# capstone_v1_1.net
KiCad netlist of a schematic drawn in Altium Designer
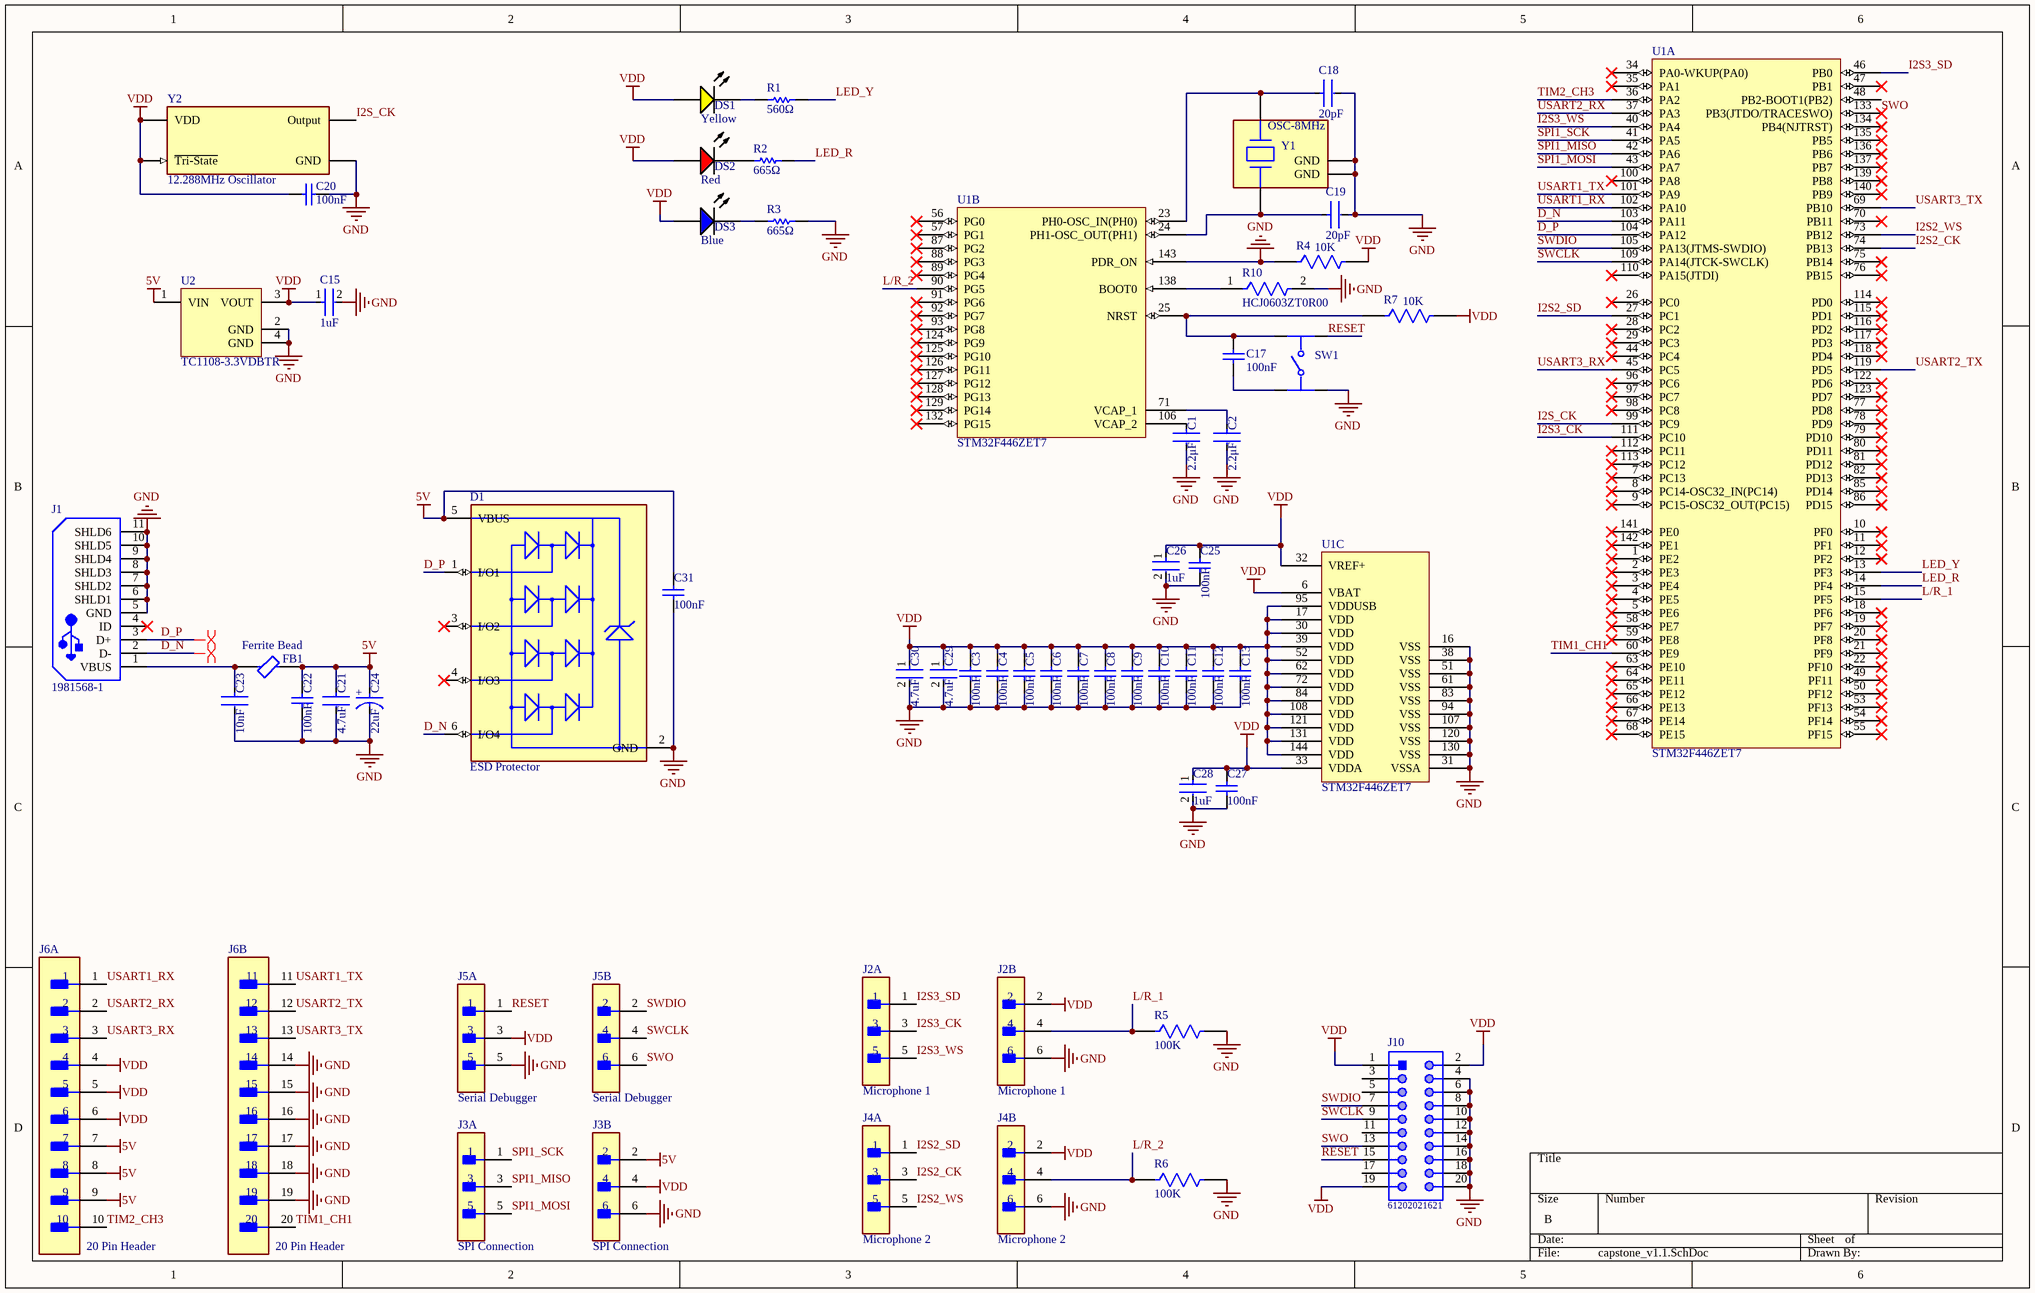
[diagram p0: capstone_v1.1.SchDoc]

(export (version "E")
  (design (tool "Eeschema 10.0.6"))
  (components
    (comp (ref "C1")
      (value "2.2μF")
      (footprint "FP-C1608-080-0_1-MFG")
      (description "Multilayer Ceramic Capacitors 2.2μF ±10% 35V X5R SMD 0603\r\nC1608X5R1V225K080AC")
      (fields (field (name "TOLERANCE") "10%") (field (name "VOLTAGE") "35V"))
      (libsource (lib "Altium Content Vault") (part "236180d848d6139a670b325ea6854c9"))
    )
    (comp (ref "C2")
      (value "2.2μF")
      (footprint "FP-C1608-080-0_1-MFG")
      (description "Multilayer Ceramic Capacitors 2.2μF ±10% 35V X5R SMD 0603\r\nC1608X5R1V225K080AC")
      (fields (field (name "TOLERANCE") "10%") (field (name "VOLTAGE") "35V"))
      (libsource (lib "Altium Content Vault") (part "236180d848d6139a670b325ea6854c9"))
    )
    (comp (ref "C3")
      (value "100nF")
      (footprint "SAMS-C0603-2_M")
      (fields (field (name "MANUFACTURER") "Samsung Electro-Mechanics"))
      (libsource (lib "Altium Content Vault") (part "CAP-NP-2"))
    )
    (comp (ref "C4")
      (value "100nF")
      (footprint "SAMS-C0603-2_M")
      (fields (field (name "MANUFACTURER") "Samsung Electro-Mechanics"))
      (libsource (lib "Altium Content Vault") (part "CAP-NP-2"))
    )
    (comp (ref "C5")
      (value "100nF")
      (footprint "SAMS-C0603-2_M")
      (fields (field (name "MANUFACTURER") "Samsung Electro-Mechanics"))
      (libsource (lib "Altium Content Vault") (part "CAP-NP-2"))
    )
    (comp (ref "C6")
      (value "100nF")
      (footprint "SAMS-C0603-2_M")
      (fields (field (name "MANUFACTURER") "Samsung Electro-Mechanics"))
      (libsource (lib "Altium Content Vault") (part "CAP-NP-2"))
    )
    (comp (ref "C7")
      (value "100nF")
      (footprint "SAMS-C0603-2_M")
      (fields (field (name "MANUFACTURER") "Samsung Electro-Mechanics"))
      (libsource (lib "Altium Content Vault") (part "CAP-NP-2"))
    )
    (comp (ref "C8")
      (value "100nF")
      (footprint "SAMS-C0603-2_M")
      (fields (field (name "MANUFACTURER") "Samsung Electro-Mechanics"))
      (libsource (lib "Altium Content Vault") (part "CAP-NP-2"))
    )
    (comp (ref "C9")
      (value "100nF")
      (footprint "SAMS-C0603-2_M")
      (fields (field (name "MANUFACTURER") "Samsung Electro-Mechanics"))
      (libsource (lib "Altium Content Vault") (part "CAP-NP-2"))
    )
    (comp (ref "C10")
      (value "100nF")
      (footprint "SAMS-C0603-2_M")
      (fields (field (name "MANUFACTURER") "Samsung Electro-Mechanics"))
      (libsource (lib "Altium Content Vault") (part "CAP-NP-2"))
    )
    (comp (ref "C11")
      (value "100nF")
      (footprint "SAMS-C0603-2_M")
      (fields (field (name "MANUFACTURER") "Samsung Electro-Mechanics"))
      (libsource (lib "Altium Content Vault") (part "CAP-NP-2"))
    )
    (comp (ref "C12")
      (value "100nF")
      (footprint "SAMS-C0603-2_M")
      (fields (field (name "MANUFACTURER") "Samsung Electro-Mechanics"))
      (libsource (lib "Altium Content Vault") (part "CAP-NP-2"))
    )
    (comp (ref "C13")
      (value "100nF")
      (footprint "SAMS-C0603-2_M")
      (fields (field (name "MANUFACTURER") "Samsung Electro-Mechanics"))
      (libsource (lib "Altium Content Vault") (part "CAP-NP-2"))
    )
    (comp (ref "C15")
      (value "1uF")
      (footprint "FP-0603-L_1_6_0_15-W_0_81-IPC_A")
      (description "General Purpose Ceramic Capacitor, 0603, 1uF, 10%, X5R, 15%, 10V\r\n0603ZD105KAT2A")
      (fields (field (name "TOLERANCE") "10%") (field (name "VOLTAGE") "10V"))
      (libsource (lib "Altium Content Vault") (part "02cd4be3c70576c341d710602a673aa"))
    )
    (comp (ref "C17")
      (value "100nF")
      (footprint "SAMS-C0603-2_M")
      (fields (field (name "MANUFACTURER") "Samsung Electro-Mechanics"))
      (libsource (lib "Altium Content Vault") (part "CAP-NP-2"))
    )
    (comp (ref "C18")
      (value "20pF")
      (footprint "FP-C0603C-CF-MFG")
      (description "CAP CER 20PF 50V 5% NP0 0603\r\nC0603C200J5GACTU")
      (fields
        (field (name "MANUFACTURER PART NUMBER") "C0603C200J5GACTU")
        (field (name "MANUFACTURER") "KEMET")
      )
      (libsource (lib "Altium Content Vault") (part "b4654b650e69147ec39a6b967a45e02"))
    )
    (comp (ref "C19")
      (value "20pF")
      (footprint "FP-C0603C-CF-MFG")
      (description "CAP CER 20PF 50V 5% NP0 0603\r\nC0603C200J5GACTU")
      (fields
        (field (name "MANUFACTURER PART NUMBER") "C0603C200J5GACTU")
        (field (name "MANUFACTURER") "KEMET")
      )
      (libsource (lib "Altium Content Vault") (part "b4654b650e69147ec39a6b967a45e02"))
    )
    (comp (ref "C20")
      (value "100nF")
      (footprint "SAMS-C0603-2_M")
      (fields (field (name "MANUFACTURER") "Samsung Electro-Mechanics"))
      (libsource (lib "Altium Content Vault") (part "CAP-NP-2"))
    )
    (comp (ref "C21")
      (value "4.7uF")
      (footprint "FP-C0603-CG-MFG")
      (description "CAP CER 4.7UF 6.3V X5R 0603\r\nC0603C475K9PACTU")
      (fields (field (name "TOLERANCE") "10%") (field (name "MANUFACTURER") "Kemet"))
      (libsource (lib "") (part "11868f565c42a9108669ba33697ecf6_1"))
    )
    (comp (ref "C22")
      (value "100nF")
      (footprint "SAMS-C0603-2_M")
      (fields (field (name "MANUFACTURER") "Samsung Electro-Mechanics"))
      (libsource (lib "Altium Content Vault") (part "CAP-NP-2"))
    )
    (comp (ref "C23")
      (value "10nF")
      (footprint "FP-0603-L_1_6_0_15-W_0_81-MFG")
      (description "General Purpose Ceramic Capacitor, 0603, 10nF, 10%, X7R, 15%, 50V")
      (fields (field (name "VOLTAGE") "50V") (field (name "TOLERANCE") "10%"))
      (libsource (lib "") (part "02cd4be3c70576c341d710602a673aa_1"))
    )
    (comp (ref "C24")
      (value "22uF")
      (footprint "FP-T491C226K010AT-MFG")
      (description "CAP TANT 22UF 10% 10V 2312\r\nT491C226K010AT")
      (fields (field (name "TOLERANCE") "20%") (field (name "VOLTAGE") "10V"))
      (libsource (lib "Altium Content Vault") (part "a00bbbee19879c290e62620ae7e47b1"))
    )
    (comp (ref "C25")
      (value "100nF")
      (footprint "SAMS-C0603-2_M")
      (fields (field (name "MANUFACTURER") "Samsung Electro-Mechanics"))
      (libsource (lib "Altium Content Vault") (part "CAP-NP-2"))
    )
    (comp (ref "C26")
      (value "1uF")
      (footprint "FP-0603-L_1_6_0_15-W_0_81-IPC_A")
      (description "General Purpose Ceramic Capacitor, 0603, 1uF, 10%, X5R, 15%, 10V\r\n0603ZD105KAT2A")
      (fields (field (name "TOLERANCE") "10%") (field (name "VOLTAGE") "10V"))
      (libsource (lib "Altium Content Vault") (part "02cd4be3c70576c341d710602a673aa"))
    )
    (comp (ref "C27")
      (value "100nF")
      (footprint "SAMS-C0603-2_M")
      (fields (field (name "MANUFACTURER") "Samsung Electro-Mechanics"))
      (libsource (lib "Altium Content Vault") (part "CAP-NP-2"))
    )
    (comp (ref "C28")
      (value "1uF")
      (footprint "FP-0603-L_1_6_0_15-W_0_81-IPC_A")
      (description "General Purpose Ceramic Capacitor, 0603, 1uF, 10%, X5R, 15%, 10V\r\n0603ZD105KAT2A")
      (fields (field (name "TOLERANCE") "10%") (field (name "VOLTAGE") "10V"))
      (libsource (lib "Altium Content Vault") (part "02cd4be3c70576c341d710602a673aa"))
    )
    (comp (ref "C29")
      (value "4.7uF")
      (footprint "FP-C0603-CG-MFG")
      (description "CAP CER 4.7UF 6.3V X5R 0603\r\nC0603C475K9PACTU")
      (fields (field (name "TOLERANCE") "10%") (field (name "MANUFACTURER") "Kemet"))
      (libsource (lib "Altium Content Vault") (part "11868f565c42a9108669ba33697ecf6"))
    )
    (comp (ref "C30")
      (value "4.7uF")
      (footprint "FP-C0603-CG-MFG")
      (description "CAP CER 4.7UF 6.3V X5R 0603\r\nC0603C475K9PACTU")
      (fields (field (name "TOLERANCE") "10%") (field (name "MANUFACTURER") "Kemet"))
      (libsource (lib "Altium Content Vault") (part "11868f565c42a9108669ba33697ecf6"))
    )
    (comp (ref "C31")
      (value "100nF")
      (footprint "SAMS-C0603-2_M")
      (fields (field (name "MANUFACTURER") "Samsung Electro-Mechanics"))
      (libsource (lib "Altium Content Vault") (part "CAP-NP-2"))
    )
    (comp (ref "D1")
      (value "ESD Protector")
      (footprint "FP-SOT23-6L-MFG")
      (description "TVS DIODE 5.25V 17V SOT23-6\r\nUSBLC6-4SC6")
      (fields
        (field (name "MANUFACTURER") "STMicroelectronics")
        (field (name "OCTOPART") "https://octopart.com/usblc6-4sc6-stmicroelectronics-347147")
      )
      (libsource (lib "Altium Content Vault") (part "3e70b616ccdc4c88b528e1820c4a7da"))
    )
    (comp (ref "DS1")
      (value "Yellow")
      (footprint "VISH-TLMY1000_V")
      (description "Low Current LED, 40 mW, -40 to 100 degC, 2-Pin SMD, RoHS, Tape and Reel\r\nTLMY1000-GS08")
      (fields (field (name "MANUFACTURER") "Vishay"))
      (libsource (lib "Altium Content Vault") (part "LED-YELLOW-AK-2"))
    )
    (comp (ref "DS2")
      (value "Red")
      (footprint "AVAG-HSMX-C190_V")
      (description "LED Uni-Color Red, 65 mW, 20 mA, -40 to 85 degC, 2-Pin SMD, RoHS, Tape and Reel\r\nHSMH-C190")
      (libsource (lib "Altium Content Vault") (part "LED-RED-AK-2"))
    )
    (comp (ref "DS3")
      (value "Blue")
      (footprint "AVAG-HSMX-C190_V")
      (description "LED Uni-Color Blue, 78 mW, 20 mA, -40 to 85 degC, 2-Pin SMD, RoHS, Tape and Reel\r\nHSMR-C190")
      (libsource (lib "Altium Content Vault") (part "LED-BLUE-AK-2"))
    )
    (comp (ref "FB1")
      (value "Ferrite Bead")
      (footprint "FP-BLM15-0_05-IPC_A")
      (description "Chip Ferrite Bead, 0402, 220Ω @ 100MHz, 0.1Ω, 25%, 1.4A\r\nBLM15PX221SN1D")
      (fields (field (name "TOLERANCE") "25%"))
      (libsource (lib "Altium Content Vault") (part "5f30dd21d616792df468990f7003faa"))
    )
    (comp (ref "J1")
      (value "1981568-1")
      (footprint "TECO-1981568-5_V")
      (description "Micro USB Receptacle Standard Type B Assy, 5-Pin SMD, RoHS, Tape and Reel")
      (fields (field (name "MANUFACTURER") "TE Connectivity"))
      (libsource (lib "Altium Content Vault") (part "USB-5-6SHLD"))
    )
    (comp (ref "J2")
      (value "Microphone 1")
      (footprint "FP-M20-9980346-MFG")
      (description "CONN HEADER VERT 6POS 2.54MM\r\nM20-9980346")
      (fields (field (name "MANUFACTURER PART NUMBER") "M20-9980346") (field (name "MANUFACTURER") "Harwin"))
      (libsource (lib "Altium Content Vault") (part "2654a11fb13586ecb194516b1c997bc"))
    )
    (comp (ref "J3")
      (value "SPI Connection")
      (footprint "FP-M20-9980346-MFG")
      (description "CONN HEADER VERT 6POS 2.54MM\r\nM20-9980346")
      (fields (field (name "MANUFACTURER PART NUMBER") "M20-9980346") (field (name "MANUFACTURER") "Harwin"))
      (libsource (lib "Altium Content Vault") (part "2654a11fb13586ecb194516b1c997bc"))
    )
    (comp (ref "J4")
      (value "Microphone 2")
      (footprint "FP-M20-9980346-MFG")
      (description "CONN HEADER VERT 6POS 2.54MM\r\nM20-9980346")
      (fields (field (name "MANUFACTURER PART NUMBER") "M20-9980346") (field (name "MANUFACTURER") "Harwin"))
      (libsource (lib "Altium Content Vault") (part "2654a11fb13586ecb194516b1c997bc"))
    )
    (comp (ref "J5")
      (value "Serial Debugger")
      (footprint "FP-M20-9980346-MFG")
      (description "CONN HEADER VERT 6POS 2.54MM\r\nM20-9980346")
      (fields (field (name "MANUFACTURER PART NUMBER") "M20-9980346") (field (name "MANUFACTURER") "Harwin"))
      (libsource (lib "Altium Content Vault") (part "2654a11fb13586ecb194516b1c997bc"))
    )
    (comp (ref "J6")
      (value "20 Pin Header")
      (footprint "FP-TSW-110-08-G-D-MFG")
      (description "CONN HEADER VERT 20POS 2.54MM\r\nTSW-110-08-G-D")
      (fields
        (field (name "MANUFACTURER") "Samtec")
        (field (name "MANUFACTURER PART NUMBER") "TSW-110-08-G-D")
      )
      (libsource (lib "Altium Content Vault") (part "77e5b6e48cf913a9c6d5f7856d88bd2"))
    )
    (comp (ref "J10")
      (value "61202021621")
      (footprint "61202021621")
      (description "Male Box Header WR-BHD, THT, Vertical, pitch 2.54 mm, 20 pins")
      (fields (field (name "MANUFACTURER") "Wurth Elektronik") (field (name "PUBLISHER") "WurthElektronik"))
      (libsource (lib "Altium Content Vault") (part "WE-CN-2P-M-R20"))
    )
    (comp (ref "R1")
      (value "560Ω")
      (footprint "RESC1608X55X30ML15T15")
      (libsource (lib "Altium Content Vault") (part "RES-2"))
    )
    (comp (ref "R2")
      (value "665Ω")
      (footprint "RESC1608X55X30ML15T15")
      (description "ERJ-3EKF6650V")
      (fields (field (name "MANUFACTURER") "Panasonic"))
      (libsource (lib "Altium Content Vault") (part "RES"))
    )
    (comp (ref "R3")
      (value "665Ω")
      (footprint "RESC1608X55X30ML15T15")
      (description "ERJ-3EKF6650V")
      (fields (field (name "MANUFACTURER") "Panasonic"))
      (libsource (lib "Altium Content Vault") (part "RES"))
    )
    (comp (ref "R4")
      (value "10K")
      (footprint "FP-MCT0603-IPC_C")
      (description "RES SMD 100 OHM 1% 1/8W 0603\r\nMCT06030C1002FP500")
      (fields (field (name "TOLERANCE") "1%"))
      (libsource (lib "Altium Content Vault") (part "1029c3af85768c4190bb7ad29bc67b5"))
    )
    (comp (ref "R5")
      (value "100K")
      (footprint "FP-RC0603-0_55-MFG")
      (description "RES SMD 100K OHM 1% 1/10W 0603\r\nRC0603FR-07100KL")
      (fields (field (name "TOLERANCE") "1%"))
      (libsource (lib "Altium Content Vault") (part "1029c3af85768c4190bb7ad29bc67b5"))
    )
    (comp (ref "R6")
      (value "100K")
      (footprint "FP-RC0603-0_55-MFG")
      (description "RES SMD 100K OHM 1% 1/10W 0603\r\nRC0603FR-07100KL")
      (fields (field (name "TOLERANCE") "1%"))
      (libsource (lib "Altium Content Vault") (part "1029c3af85768c4190bb7ad29bc67b5"))
    )
    (comp (ref "R7")
      (value "10K")
      (footprint "FP-MCT0603-IPC_C")
      (description "RES SMD 100 OHM 1% 1/8W 0603\r\nMCT06030C1002FP500")
      (fields (field (name "TOLERANCE") "1%"))
      (libsource (lib "Altium Content Vault") (part "1029c3af85768c4190bb7ad29bc67b5"))
    )
    (comp (ref "R10")
      (value "HCJ0603ZT0R00")
      (footprint "FP-HCJ0603-MFG")
      (description "RES 0 OHM JUMPER 1/4W 0603")
      (libsource (lib "") (part "1029c3af85768c4190bb7ad29bc67b5_1"))
    )
    (comp (ref "SW1")
      (value "PTS645SM43SMTR92LFS")
      (footprint "FP-PTS645SM43SMTR92LFS-MFG")
      (description "SWITCH TACTILE SPST-NO 0.05A 12V")
      (libsource (lib "Altium Content Vault") (part "1adf0dd01260c80cf25a44bfd6b99ba"))
    )
    (comp (ref "U1")
      (value "STM32F446ZET7")
      (footprint "STM-LQFP144_M")
      (libsource (lib "Altium Content Vault") (part "MC-ARM-STM32F446-LQFP144"))
    )
    (comp (ref "U2")
      (value "TC1108-3.3VDBTR")
      (footprint "SOT-223-DB3_L")
      (description "300mA CMOS LDO, 3-Pin SOT-223, Extended Temperature, Tape and Reel")
      (libsource (lib "Altium Content Vault") (part "PM-LINEREG-TC1108-IL4"))
    )
    (comp (ref "Y1")
      (value "OSC-8MHz")
      (footprint "FP-ABM3B-MFG")
      (description "Crystal 8MHz ±20ppm 18pF SMD-4 5mm x 3.2mm\r\nABM3B-8.000MHZ-B2-T")
      (fields (field (name "TOLERANCE") "20ppm"))
      (libsource (lib "Altium Content Vault") (part "48e526d86b7f2615d98721063c72f49"))
    )
    (comp (ref "Y2")
      (value "12.288MHz Oscillator")
      (footprint "FP-ASFL1-MFG")
      (description "XTAL Oscillator 12.288MHz ±50ppm HCMOS, TTL 3.3V 4-SMD 5mm x 3.2mm\r\nASFL1-12.288MHZ-EC-T")
      (libsource (lib "Altium Content Vault") (part "47df00dc2349451232cb22fac08fbff"))
    )
  )
  (nets
    (net (code "1") (name "/D_N") (class "Default")
      (node (ref "D1") (pin "6") (pinfunction "I/O4_6") (pintype "bidirectional"))
      (node (ref "J1") (pin "2") (pinfunction "D-_2") (pintype "passive"))
      (node (ref "U1") (pin "103") (pinfunction "PA11_103") (pintype "bidirectional"))
    )
    (net (code "2") (name "/D_P") (class "Default")
      (node (ref "D1") (pin "1") (pinfunction "I/O1_1") (pintype "bidirectional"))
      (node (ref "J1") (pin "3") (pinfunction "D+_3") (pintype "passive"))
      (node (ref "U1") (pin "104") (pinfunction "PA12_104") (pintype "bidirectional"))
    )
    (net (code "3") (name "/I2S2_CK") (class "Default")
      (node (ref "J4") (pin "3") (pinfunction "3_3") (pintype "passive"))
      (node (ref "U1") (pin "74") (pinfunction "PB13_74") (pintype "bidirectional"))
    )
    (net (code "4") (name "/I2S2_SD") (class "Default")
      (node (ref "J4") (pin "1") (pinfunction "1_1") (pintype "passive"))
      (node (ref "U1") (pin "27") (pinfunction "PC1_27") (pintype "bidirectional"))
    )
    (net (code "5") (name "/I2S2_WS") (class "Default")
      (node (ref "J4") (pin "5") (pinfunction "5_5") (pintype "passive"))
      (node (ref "U1") (pin "73") (pinfunction "PB12_73") (pintype "bidirectional"))
    )
    (net (code "6") (name "/I2S3_CK") (class "Default")
      (node (ref "J2") (pin "3") (pinfunction "3_3") (pintype "passive"))
      (node (ref "U1") (pin "111") (pinfunction "PC10_111") (pintype "bidirectional"))
    )
    (net (code "7") (name "/I2S3_SD") (class "Default")
      (node (ref "J2") (pin "1") (pinfunction "1_1") (pintype "passive"))
      (node (ref "U1") (pin "46") (pinfunction "PB0_46") (pintype "bidirectional"))
    )
    (net (code "8") (name "/I2S3_WS") (class "Default")
      (node (ref "J2") (pin "5") (pinfunction "5_5") (pintype "passive"))
      (node (ref "U1") (pin "40") (pinfunction "PA4_40") (pintype "bidirectional"))
    )
    (net (code "9") (name "/I2S_CK") (class "Default")
      (node (ref "U1") (pin "99") (pinfunction "PC9_99") (pintype "bidirectional"))
      (node (ref "Y2") (pin "3") (pinfunction "Output_3") (pintype "passive"))
    )
    (net (code "10") (name "/LED_R") (class "Default")
      (node (ref "R2") (pin "2") (pinfunction "2_2") (pintype "passive"))
      (node (ref "U1") (pin "14") (pinfunction "PF4_14") (pintype "bidirectional"))
    )
    (net (code "11") (name "/LED_Y") (class "Default")
      (node (ref "R1") (pin "2") (pinfunction "2_2") (pintype "passive"))
      (node (ref "U1") (pin "13") (pinfunction "PF3_13") (pintype "bidirectional"))
    )
    (net (code "12") (name "/L{slash}R_1") (class "Default")
      (node (ref "J2") (pin "4") (pinfunction "4_4") (pintype "passive"))
      (node (ref "R5") (pin "1") (pinfunction "1_1") (pintype "passive"))
      (node (ref "U1") (pin "15") (pinfunction "PF5_15") (pintype "bidirectional"))
    )
    (net (code "13") (name "/L{slash}R_2") (class "Default")
      (node (ref "J4") (pin "4") (pinfunction "4_4") (pintype "passive"))
      (node (ref "R6") (pin "1") (pinfunction "1_1") (pintype "passive"))
      (node (ref "U1") (pin "90") (pinfunction "PG5_90") (pintype "bidirectional"))
    )
    (net (code "14") (name "/RESET") (class "Default")
      (node (ref "J10") (pin "15") (pinfunction "15_15") (pintype "passive"))
      (node (ref "J5") (pin "1") (pinfunction "1_1") (pintype "passive"))
      (node (ref "SW1") (pin "2") (pinfunction "2_2") (pintype "passive"))
    )
    (net (code "15") (name "/SPI1_MISO") (class "Default")
      (node (ref "J3") (pin "3") (pinfunction "3_3") (pintype "passive"))
      (node (ref "U1") (pin "42") (pinfunction "PA6_42") (pintype "bidirectional"))
    )
    (net (code "16") (name "/SPI1_MOSI") (class "Default")
      (node (ref "J3") (pin "5") (pinfunction "5_5") (pintype "passive"))
      (node (ref "U1") (pin "43") (pinfunction "PA7_43") (pintype "bidirectional"))
    )
    (net (code "17") (name "/SPI1_SCK") (class "Default")
      (node (ref "J3") (pin "1") (pinfunction "1_1") (pintype "passive"))
      (node (ref "U1") (pin "41") (pinfunction "PA5_41") (pintype "bidirectional"))
    )
    (net (code "18") (name "/SWCLK") (class "Default")
      (node (ref "J10") (pin "9") (pinfunction "9_9") (pintype "passive"))
      (node (ref "J5") (pin "4") (pinfunction "4_4") (pintype "passive"))
      (node (ref "U1") (pin "109") (pinfunction "PA14(JTCK-SWCLK)_109") (pintype "bidirectional"))
    )
    (net (code "19") (name "/SWDIO") (class "Default")
      (node (ref "J10") (pin "7") (pinfunction "7_7") (pintype "passive"))
      (node (ref "J5") (pin "2") (pinfunction "2_2") (pintype "passive"))
      (node (ref "U1") (pin "105") (pinfunction "PA13(JTMS-SWDIO)_105") (pintype "bidirectional"))
    )
    (net (code "20") (name "/SWO") (class "Default")
      (node (ref "J10") (pin "13") (pinfunction "13_13") (pintype "passive"))
      (node (ref "J5") (pin "6") (pinfunction "6_6") (pintype "passive"))
      (node (ref "U1") (pin "133") (pinfunction "PB3(JTDO/TRACESWO)_133") (pintype "bidirectional"))
    )
    (net (code "21") (name "/TIM1_CH1") (class "Default")
      (node (ref "J6") (pin "20") (pinfunction "20_20") (pintype "passive"))
      (node (ref "U1") (pin "60") (pinfunction "PE9_60") (pintype "bidirectional"))
    )
    (net (code "22") (name "/TIM2_CH3") (class "Default")
      (node (ref "J6") (pin "10") (pinfunction "10_10") (pintype "passive"))
      (node (ref "U1") (pin "36") (pinfunction "PA2_36") (pintype "bidirectional"))
    )
    (net (code "23") (name "/USART1_RX") (class "Default")
      (node (ref "J6") (pin "1") (pinfunction "1_1") (pintype "passive"))
      (node (ref "U1") (pin "102") (pinfunction "PA10_102") (pintype "bidirectional"))
    )
    (net (code "24") (name "/USART1_TX") (class "Default")
      (node (ref "J6") (pin "11") (pinfunction "11_11") (pintype "passive"))
      (node (ref "U1") (pin "101") (pinfunction "PA9_101") (pintype "bidirectional"))
    )
    (net (code "25") (name "/USART2_RX") (class "Default")
      (node (ref "J6") (pin "2") (pinfunction "2_2") (pintype "passive"))
      (node (ref "U1") (pin "37") (pinfunction "PA3_37") (pintype "bidirectional"))
    )
    (net (code "26") (name "/USART2_TX") (class "Default")
      (node (ref "J6") (pin "12") (pinfunction "12_12") (pintype "passive"))
      (node (ref "U1") (pin "119") (pinfunction "PD5_119") (pintype "bidirectional"))
    )
    (net (code "27") (name "/USART3_RX") (class "Default")
      (node (ref "J6") (pin "3") (pinfunction "3_3") (pintype "passive"))
      (node (ref "U1") (pin "45") (pinfunction "PC5_45") (pintype "bidirectional"))
    )
    (net (code "28") (name "/USART3_TX") (class "Default")
      (node (ref "J6") (pin "13") (pinfunction "13_13") (pintype "passive"))
      (node (ref "U1") (pin "69") (pinfunction "PB10_69") (pintype "bidirectional"))
    )
    (net (code "29") (name "5V") (class "Default")
      (node (ref "C21") (pin "1") (pinfunction "1_1") (pintype "passive"))
      (node (ref "C22") (pin "2") (pinfunction "2_2") (pintype "passive"))
      (node (ref "C24") (pin "2") (pinfunction "A_2") (pintype "passive"))
      (node (ref "C31") (pin "2") (pinfunction "2_2") (pintype "passive"))
      (node (ref "D1") (pin "5") (pinfunction "VBUS_5") (pintype "power_in"))
      (node (ref "FB1") (pin "2") (pinfunction "2_2") (pintype "passive"))
      (node (ref "J3") (pin "2") (pinfunction "2_2") (pintype "passive"))
      (node (ref "J6") (pin "7") (pinfunction "7_7") (pintype "passive"))
      (node (ref "J6") (pin "8") (pinfunction "8_8") (pintype "passive"))
      (node (ref "J6") (pin "9") (pinfunction "9_9") (pintype "passive"))
      (node (ref "U2") (pin "1") (pinfunction "VIN_1") (pintype "power_in"))
    )
    (net (code "30") (name "GND") (class "Default")
      (node (ref "C1") (pin "1") (pinfunction "1_1") (pintype "passive"))
      (node (ref "C10") (pin "1") (pinfunction "1_1") (pintype "passive"))
      (node (ref "C11") (pin "1") (pinfunction "1_1") (pintype "passive"))
      (node (ref "C12") (pin "1") (pinfunction "1_1") (pintype "passive"))
      (node (ref "C13") (pin "1") (pinfunction "1_1") (pintype "passive"))
      (node (ref "C15") (pin "2") (pinfunction "2_2") (pintype "passive"))
      (node (ref "C18") (pin "2") (pinfunction "2_2") (pintype "passive"))
      (node (ref "C19") (pin "2") (pinfunction "2_2") (pintype "passive"))
      (node (ref "C2") (pin "1") (pinfunction "1_1") (pintype "passive"))
      (node (ref "C20") (pin "1") (pinfunction "1_1") (pintype "passive"))
      (node (ref "C21") (pin "2") (pinfunction "2_2") (pintype "passive"))
      (node (ref "C22") (pin "1") (pinfunction "1_1") (pintype "passive"))
      (node (ref "C23") (pin "2") (pinfunction "2_2") (pintype "passive"))
      (node (ref "C24") (pin "1") (pinfunction "C_1") (pintype "passive"))
      (node (ref "C25") (pin "1") (pinfunction "1_1") (pintype "passive"))
      (node (ref "C26") (pin "2") (pinfunction "2_2") (pintype "passive"))
      (node (ref "C27") (pin "1") (pinfunction "1_1") (pintype "passive"))
      (node (ref "C28") (pin "2") (pinfunction "2_2") (pintype "passive"))
      (node (ref "C29") (pin "2") (pinfunction "2_2") (pintype "passive"))
      (node (ref "C3") (pin "1") (pinfunction "1_1") (pintype "passive"))
      (node (ref "C30") (pin "2") (pinfunction "2_2") (pintype "passive"))
      (node (ref "C31") (pin "1") (pinfunction "1_1") (pintype "passive"))
      (node (ref "C4") (pin "1") (pinfunction "1_1") (pintype "passive"))
      (node (ref "C5") (pin "1") (pinfunction "1_1") (pintype "passive"))
      (node (ref "C6") (pin "1") (pinfunction "1_1") (pintype "passive"))
      (node (ref "C7") (pin "1") (pinfunction "1_1") (pintype "passive"))
      (node (ref "C8") (pin "1") (pinfunction "1_1") (pintype "passive"))
      (node (ref "C9") (pin "1") (pinfunction "1_1") (pintype "passive"))
      (node (ref "D1") (pin "2") (pinfunction "GND_2") (pintype "power_in"))
      (node (ref "J1") (pin "10") (pinfunction "SHLD5_10") (pintype "passive"))
      (node (ref "J1") (pin "11") (pinfunction "SHLD6_11") (pintype "passive"))
      (node (ref "J1") (pin "5") (pinfunction "GND_5") (pintype "passive"))
      (node (ref "J1") (pin "6") (pinfunction "SHLD1_6") (pintype "passive"))
      (node (ref "J1") (pin "7") (pinfunction "SHLD2_7") (pintype "passive"))
      (node (ref "J1") (pin "8") (pinfunction "SHLD3_8") (pintype "passive"))
      (node (ref "J1") (pin "9") (pinfunction "SHLD4_9") (pintype "passive"))
      (node (ref "J10") (pin "10") (pinfunction "10_10") (pintype "passive"))
      (node (ref "J10") (pin "12") (pinfunction "12_12") (pintype "passive"))
      (node (ref "J10") (pin "14") (pinfunction "14_14") (pintype "passive"))
      (node (ref "J10") (pin "16") (pinfunction "16_16") (pintype "passive"))
      (node (ref "J10") (pin "18") (pinfunction "18_18") (pintype "passive"))
      (node (ref "J10") (pin "20") (pinfunction "20_20") (pintype "passive"))
      (node (ref "J10") (pin "4") (pinfunction "4_4") (pintype "passive"))
      (node (ref "J10") (pin "6") (pinfunction "6_6") (pintype "passive"))
      (node (ref "J10") (pin "8") (pinfunction "8_8") (pintype "passive"))
      (node (ref "J2") (pin "6") (pinfunction "6_6") (pintype "passive"))
      (node (ref "J3") (pin "6") (pinfunction "6_6") (pintype "passive"))
      (node (ref "J4") (pin "6") (pinfunction "6_6") (pintype "passive"))
      (node (ref "J5") (pin "5") (pinfunction "5_5") (pintype "passive"))
      (node (ref "J6") (pin "14") (pinfunction "14_14") (pintype "passive"))
      (node (ref "J6") (pin "15") (pinfunction "15_15") (pintype "passive"))
      (node (ref "J6") (pin "16") (pinfunction "16_16") (pintype "passive"))
      (node (ref "J6") (pin "17") (pinfunction "17_17") (pintype "passive"))
      (node (ref "J6") (pin "18") (pinfunction "18_18") (pintype "passive"))
      (node (ref "J6") (pin "19") (pinfunction "19_19") (pintype "passive"))
      (node (ref "R10") (pin "2") (pinfunction "2_2") (pintype "passive"))
      (node (ref "R3") (pin "2") (pinfunction "2_2") (pintype "passive"))
      (node (ref "R4") (pin "1") (pinfunction "1_1") (pintype "passive"))
      (node (ref "R5") (pin "2") (pinfunction "2_2") (pintype "passive"))
      (node (ref "R6") (pin "2") (pinfunction "2_2") (pintype "passive"))
      (node (ref "SW1") (pin "4") (pinfunction "4_4") (pintype "passive"))
      (node (ref "U1") (pin "107") (pinfunction "VSS_107") (pintype "power_in"))
      (node (ref "U1") (pin "120") (pinfunction "VSS_120") (pintype "power_in"))
      (node (ref "U1") (pin "130") (pinfunction "VSS_130") (pintype "power_in"))
      (node (ref "U1") (pin "143") (pinfunction "PDR_ON_143") (pintype "input"))
      (node (ref "U1") (pin "16") (pinfunction "VSS_16") (pintype "power_in"))
      (node (ref "U1") (pin "31") (pinfunction "VSSA_31") (pintype "power_in"))
      (node (ref "U1") (pin "38") (pinfunction "VSS_38") (pintype "power_in"))
      (node (ref "U1") (pin "51") (pinfunction "VSS_51") (pintype "power_in"))
      (node (ref "U1") (pin "61") (pinfunction "VSS_61") (pintype "power_in"))
      (node (ref "U1") (pin "83") (pinfunction "VSS_83") (pintype "power_in"))
      (node (ref "U1") (pin "94") (pinfunction "VSS_94") (pintype "power_in"))
      (node (ref "U2") (pin "2") (pinfunction "GND_2") (pintype "power_in"))
      (node (ref "U2") (pin "4") (pinfunction "GND_4") (pintype "power_in"))
      (node (ref "Y1") (pin "2") (pinfunction "GND_2") (pintype "power_in"))
      (node (ref "Y1") (pin "4") (pinfunction "GND_4") (pintype "power_in"))
      (node (ref "Y2") (pin "2") (pinfunction "GND_2") (pintype "power_in"))
    )
    (net (code "31") (name "Net-(C17-Pad1)") (class "Default")
      (node (ref "C17") (pin "1") (pinfunction "1_1") (pintype "passive"))
      (node (ref "SW1") (pin "3") (pinfunction "3_3") (pintype "passive"))
    )
    (net (code "32") (name "Net-(DS1-K)") (class "Default")
      (node (ref "DS1") (pin "2") (pinfunction "K_2") (pintype "passive"))
      (node (ref "R1") (pin "1") (pinfunction "1_1") (pintype "passive"))
    )
    (net (code "33") (name "Net-(DS2-K)") (class "Default")
      (node (ref "DS2") (pin "2") (pinfunction "K_2") (pintype "passive"))
      (node (ref "R2") (pin "1") (pinfunction "1_1") (pintype "passive"))
    )
    (net (code "34") (name "Net-(DS3-K)") (class "Default")
      (node (ref "DS3") (pin "2") (pinfunction "K_2") (pintype "passive"))
      (node (ref "R3") (pin "1") (pinfunction "1_1") (pintype "passive"))
    )
    (net (code "35") (name "Net-(J1-VBUS)") (class "Default")
      (node (ref "C23") (pin "1") (pinfunction "1_1") (pintype "passive"))
      (node (ref "FB1") (pin "1") (pinfunction "1_1") (pintype "passive"))
      (node (ref "J1") (pin "1") (pinfunction "VBUS_1") (pintype "passive"))
    )
    (net (code "36") (name "Net-(U1B-BOOT0)") (class "Default")
      (node (ref "R10") (pin "1") (pinfunction "1_1") (pintype "passive"))
      (node (ref "U1") (pin "138") (pinfunction "BOOT0_138") (pintype "input"))
    )
    (net (code "37") (name "Net-(U1B-NRST)") (class "Default")
      (node (ref "C17") (pin "2") (pinfunction "2_2") (pintype "passive"))
      (node (ref "R7") (pin "1") (pinfunction "1_1") (pintype "passive"))
      (node (ref "SW1") (pin "1") (pinfunction "1_1") (pintype "passive"))
      (node (ref "U1") (pin "25") (pinfunction "NRST_25") (pintype "bidirectional"))
    )
    (net (code "38") (name "Net-(U1B-PH0-OSC_IN(PH0))") (class "Default")
      (node (ref "C18") (pin "1") (pinfunction "1_1") (pintype "passive"))
      (node (ref "U1") (pin "23") (pinfunction "PH0-OSC_IN(PH0)_23") (pintype "bidirectional"))
      (node (ref "Y1") (pin "1") (pinfunction "1_1") (pintype "passive"))
    )
    (net (code "39") (name "Net-(U1B-PH1-OSC_OUT(PH1))") (class "Default")
      (node (ref "C19") (pin "1") (pinfunction "1_1") (pintype "passive"))
      (node (ref "U1") (pin "24") (pinfunction "PH1-OSC_OUT(PH1)_24") (pintype "bidirectional"))
      (node (ref "Y1") (pin "3") (pinfunction "3_3") (pintype "passive"))
    )
    (net (code "40") (name "Net-(U1B-VCAP_1)") (class "Default")
      (node (ref "C2") (pin "2") (pinfunction "2_2") (pintype "passive"))
      (node (ref "U1") (pin "71") (pinfunction "VCAP_1_71") (pintype "passive"))
    )
    (net (code "41") (name "Net-(U1B-VCAP_2)") (class "Default")
      (node (ref "C1") (pin "2") (pinfunction "2_2") (pintype "passive"))
      (node (ref "U1") (pin "106") (pinfunction "VCAP_2_106") (pintype "passive"))
    )
    (net (code "42") (name "VDD") (class "Default")
      (node (ref "C10") (pin "2") (pinfunction "2_2") (pintype "passive"))
      (node (ref "C11") (pin "2") (pinfunction "2_2") (pintype "passive"))
      (node (ref "C12") (pin "2") (pinfunction "2_2") (pintype "passive"))
      (node (ref "C13") (pin "2") (pinfunction "2_2") (pintype "passive"))
      (node (ref "C15") (pin "1") (pinfunction "1_1") (pintype "passive"))
      (node (ref "C20") (pin "2") (pinfunction "2_2") (pintype "passive"))
      (node (ref "C25") (pin "2") (pinfunction "2_2") (pintype "passive"))
      (node (ref "C26") (pin "1") (pinfunction "1_1") (pintype "passive"))
      (node (ref "C27") (pin "2") (pinfunction "2_2") (pintype "passive"))
      (node (ref "C28") (pin "1") (pinfunction "1_1") (pintype "passive"))
      (node (ref "C29") (pin "1") (pinfunction "1_1") (pintype "passive"))
      (node (ref "C3") (pin "2") (pinfunction "2_2") (pintype "passive"))
      (node (ref "C30") (pin "1") (pinfunction "1_1") (pintype "passive"))
      (node (ref "C4") (pin "2") (pinfunction "2_2") (pintype "passive"))
      (node (ref "C5") (pin "2") (pinfunction "2_2") (pintype "passive"))
      (node (ref "C6") (pin "2") (pinfunction "2_2") (pintype "passive"))
      (node (ref "C7") (pin "2") (pinfunction "2_2") (pintype "passive"))
      (node (ref "C8") (pin "2") (pinfunction "2_2") (pintype "passive"))
      (node (ref "C9") (pin "2") (pinfunction "2_2") (pintype "passive"))
      (node (ref "DS1") (pin "1") (pinfunction "A_1") (pintype "passive"))
      (node (ref "DS2") (pin "1") (pinfunction "A_1") (pintype "passive"))
      (node (ref "DS3") (pin "1") (pinfunction "A_1") (pintype "passive"))
      (node (ref "J10") (pin "1") (pinfunction "1_1") (pintype "passive"))
      (node (ref "J10") (pin "19") (pinfunction "19_19") (pintype "passive"))
      (node (ref "J10") (pin "2") (pinfunction "2_2") (pintype "passive"))
      (node (ref "J2") (pin "2") (pinfunction "2_2") (pintype "passive"))
      (node (ref "J3") (pin "4") (pinfunction "4_4") (pintype "passive"))
      (node (ref "J4") (pin "2") (pinfunction "2_2") (pintype "passive"))
      (node (ref "J5") (pin "3") (pinfunction "3_3") (pintype "passive"))
      (node (ref "J6") (pin "4") (pinfunction "4_4") (pintype "passive"))
      (node (ref "J6") (pin "5") (pinfunction "5_5") (pintype "passive"))
      (node (ref "J6") (pin "6") (pinfunction "6_6") (pintype "passive"))
      (node (ref "R4") (pin "2") (pinfunction "2_2") (pintype "passive"))
      (node (ref "R7") (pin "2") (pinfunction "2_2") (pintype "passive"))
      (node (ref "U1") (pin "108") (pinfunction "VDD_108") (pintype "power_in"))
      (node (ref "U1") (pin "121") (pinfunction "VDD_121") (pintype "power_in"))
      (node (ref "U1") (pin "131") (pinfunction "VDD_131") (pintype "power_in"))
      (node (ref "U1") (pin "144") (pinfunction "VDD_144") (pintype "power_in"))
      (node (ref "U1") (pin "17") (pinfunction "VDD_17") (pintype "power_in"))
      (node (ref "U1") (pin "30") (pinfunction "VDD_30") (pintype "power_in"))
      (node (ref "U1") (pin "32") (pinfunction "VREF+_32") (pintype "power_in"))
      (node (ref "U1") (pin "33") (pinfunction "VDDA_33") (pintype "power_in"))
      (node (ref "U1") (pin "39") (pinfunction "VDD_39") (pintype "power_in"))
      (node (ref "U1") (pin "52") (pinfunction "VDD_52") (pintype "power_in"))
      (node (ref "U1") (pin "6") (pinfunction "VBAT_6") (pintype "power_in"))
      (node (ref "U1") (pin "62") (pinfunction "VDD_62") (pintype "power_in"))
      (node (ref "U1") (pin "72") (pinfunction "VDD_72") (pintype "power_in"))
      (node (ref "U1") (pin "84") (pinfunction "VDD_84") (pintype "power_in"))
      (node (ref "U1") (pin "95") (pinfunction "VDDUSB_95") (pintype "power_in"))
      (node (ref "U2") (pin "3") (pinfunction "VOUT_3") (pintype "power_in"))
      (node (ref "Y2") (pin "1") (pinfunction "~{Tri-State}_1") (pintype "input"))
      (node (ref "Y2") (pin "4") (pinfunction "VDD_4") (pintype "power_in"))
    )
    (net (code "43") (name "unconnected-(D1-I{slash}O2-Pad3)") (class "Default")
      (node (ref "D1") (pin "3") (pinfunction "I/O2_3") (pintype "bidirectional+no_connect"))
    )
    (net (code "44") (name "unconnected-(D1-I{slash}O3-Pad4)") (class "Default")
      (node (ref "D1") (pin "4") (pinfunction "I/O3_4") (pintype "bidirectional+no_connect"))
    )
    (net (code "45") (name "unconnected-(J1-ID-Pad4)") (class "Default")
      (node (ref "J1") (pin "4") (pinfunction "ID_4") (pintype "passive+no_connect"))
    )
    (net (code "46") (name "unconnected-(J10-Pad3)") (class "Default")
      (node (ref "J10") (pin "3") (pinfunction "3_3") (pintype "passive"))
    )
    (net (code "47") (name "unconnected-(J10-Pad5)") (class "Default")
      (node (ref "J10") (pin "5") (pinfunction "5_5") (pintype "passive"))
    )
    (net (code "48") (name "unconnected-(J10-Pad11)") (class "Default")
      (node (ref "J10") (pin "11") (pinfunction "11_11") (pintype "passive"))
    )
    (net (code "49") (name "unconnected-(J10-Pad17)") (class "Default")
      (node (ref "J10") (pin "17") (pinfunction "17_17") (pintype "passive"))
    )
    (net (code "50") (name "unconnected-(U1A-PA0-WKUP(PA0)-Pad34)") (class "Default")
      (node (ref "U1") (pin "34") (pinfunction "PA0-WKUP(PA0)_34") (pintype "bidirectional+no_connect"))
    )
    (net (code "51") (name "unconnected-(U1A-PA1-Pad35)") (class "Default")
      (node (ref "U1") (pin "35") (pinfunction "PA1_35") (pintype "bidirectional+no_connect"))
    )
    (net (code "52") (name "unconnected-(U1A-PA8-Pad100)") (class "Default")
      (node (ref "U1") (pin "100") (pinfunction "PA8_100") (pintype "bidirectional+no_connect"))
    )
    (net (code "53") (name "unconnected-(U1A-PA15(JTDI)-Pad110)") (class "Default")
      (node (ref "U1") (pin "110") (pinfunction "PA15(JTDI)_110") (pintype "bidirectional+no_connect"))
    )
    (net (code "54") (name "unconnected-(U1A-PB1-Pad47)") (class "Default")
      (node (ref "U1") (pin "47") (pinfunction "PB1_47") (pintype "bidirectional+no_connect"))
    )
    (net (code "55") (name "unconnected-(U1A-PB2-BOOT1(PB2)-Pad48)") (class "Default")
      (node (ref "U1") (pin "48") (pinfunction "PB2-BOOT1(PB2)_48") (pintype "bidirectional"))
    )
    (net (code "56") (name "unconnected-(U1A-PB4(NJTRST)-Pad134)") (class "Default")
      (node (ref "U1") (pin "134") (pinfunction "PB4(NJTRST)_134") (pintype "bidirectional+no_connect"))
    )
    (net (code "57") (name "unconnected-(U1A-PB5-Pad135)") (class "Default")
      (node (ref "U1") (pin "135") (pinfunction "PB5_135") (pintype "bidirectional+no_connect"))
    )
    (net (code "58") (name "unconnected-(U1A-PB6-Pad136)") (class "Default")
      (node (ref "U1") (pin "136") (pinfunction "PB6_136") (pintype "bidirectional+no_connect"))
    )
    (net (code "59") (name "unconnected-(U1A-PB7-Pad137)") (class "Default")
      (node (ref "U1") (pin "137") (pinfunction "PB7_137") (pintype "bidirectional+no_connect"))
    )
    (net (code "60") (name "unconnected-(U1A-PB8-Pad139)") (class "Default")
      (node (ref "U1") (pin "139") (pinfunction "PB8_139") (pintype "bidirectional+no_connect"))
    )
    (net (code "61") (name "unconnected-(U1A-PB9-Pad140)") (class "Default")
      (node (ref "U1") (pin "140") (pinfunction "PB9_140") (pintype "bidirectional+no_connect"))
    )
    (net (code "62") (name "unconnected-(U1A-PB11-Pad70)") (class "Default")
      (node (ref "U1") (pin "70") (pinfunction "PB11_70") (pintype "bidirectional+no_connect"))
    )
    (net (code "63") (name "unconnected-(U1A-PB14-Pad75)") (class "Default")
      (node (ref "U1") (pin "75") (pinfunction "PB14_75") (pintype "bidirectional+no_connect"))
    )
    (net (code "64") (name "unconnected-(U1A-PB15-Pad76)") (class "Default")
      (node (ref "U1") (pin "76") (pinfunction "PB15_76") (pintype "bidirectional+no_connect"))
    )
    (net (code "65") (name "unconnected-(U1A-PC0-Pad26)") (class "Default")
      (node (ref "U1") (pin "26") (pinfunction "PC0_26") (pintype "bidirectional+no_connect"))
    )
    (net (code "66") (name "unconnected-(U1A-PC2-Pad28)") (class "Default")
      (node (ref "U1") (pin "28") (pinfunction "PC2_28") (pintype "bidirectional+no_connect"))
    )
    (net (code "67") (name "unconnected-(U1A-PC3-Pad29)") (class "Default")
      (node (ref "U1") (pin "29") (pinfunction "PC3_29") (pintype "bidirectional+no_connect"))
    )
    (net (code "68") (name "unconnected-(U1A-PC4-Pad44)") (class "Default")
      (node (ref "U1") (pin "44") (pinfunction "PC4_44") (pintype "bidirectional+no_connect"))
    )
    (net (code "69") (name "unconnected-(U1A-PC6-Pad96)") (class "Default")
      (node (ref "U1") (pin "96") (pinfunction "PC6_96") (pintype "bidirectional+no_connect"))
    )
    (net (code "70") (name "unconnected-(U1A-PC7-Pad97)") (class "Default")
      (node (ref "U1") (pin "97") (pinfunction "PC7_97") (pintype "bidirectional+no_connect"))
    )
    (net (code "71") (name "unconnected-(U1A-PC8-Pad98)") (class "Default")
      (node (ref "U1") (pin "98") (pinfunction "PC8_98") (pintype "bidirectional+no_connect"))
    )
    (net (code "72") (name "unconnected-(U1A-PC11-Pad112)") (class "Default")
      (node (ref "U1") (pin "112") (pinfunction "PC11_112") (pintype "bidirectional+no_connect"))
    )
    (net (code "73") (name "unconnected-(U1A-PC12-Pad113)") (class "Default")
      (node (ref "U1") (pin "113") (pinfunction "PC12_113") (pintype "bidirectional+no_connect"))
    )
    (net (code "74") (name "unconnected-(U1A-PC13-Pad7)") (class "Default")
      (node (ref "U1") (pin "7") (pinfunction "PC13_7") (pintype "bidirectional+no_connect"))
    )
    (net (code "75") (name "unconnected-(U1A-PC14-OSC32_IN(PC14)-Pad8)") (class "Default")
      (node (ref "U1") (pin "8") (pinfunction "PC14-OSC32_IN(PC14)_8") (pintype "bidirectional+no_connect"))
    )
    (net (code "76") (name "unconnected-(U1A-PC15-OSC32_OUT(PC15)-Pad9)") (class "Default")
      (node (ref "U1") (pin "9") (pinfunction "PC15-OSC32_OUT(PC15)_9") (pintype "bidirectional+no_connect"))
    )
    (net (code "77") (name "unconnected-(U1A-PD0-Pad114)") (class "Default")
      (node (ref "U1") (pin "114") (pinfunction "PD0_114") (pintype "bidirectional+no_connect"))
    )
    (net (code "78") (name "unconnected-(U1A-PD1-Pad115)") (class "Default")
      (node (ref "U1") (pin "115") (pinfunction "PD1_115") (pintype "bidirectional+no_connect"))
    )
    (net (code "79") (name "unconnected-(U1A-PD2-Pad116)") (class "Default")
      (node (ref "U1") (pin "116") (pinfunction "PD2_116") (pintype "bidirectional+no_connect"))
    )
    (net (code "80") (name "unconnected-(U1A-PD3-Pad117)") (class "Default")
      (node (ref "U1") (pin "117") (pinfunction "PD3_117") (pintype "bidirectional+no_connect"))
    )
    (net (code "81") (name "unconnected-(U1A-PD4-Pad118)") (class "Default")
      (node (ref "U1") (pin "118") (pinfunction "PD4_118") (pintype "bidirectional+no_connect"))
    )
    (net (code "82") (name "unconnected-(U1A-PD6-Pad122)") (class "Default")
      (node (ref "U1") (pin "122") (pinfunction "PD6_122") (pintype "bidirectional+no_connect"))
    )
    (net (code "83") (name "unconnected-(U1A-PD7-Pad123)") (class "Default")
      (node (ref "U1") (pin "123") (pinfunction "PD7_123") (pintype "bidirectional+no_connect"))
    )
    (net (code "84") (name "unconnected-(U1A-PD8-Pad77)") (class "Default")
      (node (ref "U1") (pin "77") (pinfunction "PD8_77") (pintype "bidirectional+no_connect"))
    )
    (net (code "85") (name "unconnected-(U1A-PD9-Pad78)") (class "Default")
      (node (ref "U1") (pin "78") (pinfunction "PD9_78") (pintype "bidirectional+no_connect"))
    )
    (net (code "86") (name "unconnected-(U1A-PD10-Pad79)") (class "Default")
      (node (ref "U1") (pin "79") (pinfunction "PD10_79") (pintype "bidirectional+no_connect"))
    )
    (net (code "87") (name "unconnected-(U1A-PD11-Pad80)") (class "Default")
      (node (ref "U1") (pin "80") (pinfunction "PD11_80") (pintype "bidirectional+no_connect"))
    )
    (net (code "88") (name "unconnected-(U1A-PD12-Pad81)") (class "Default")
      (node (ref "U1") (pin "81") (pinfunction "PD12_81") (pintype "bidirectional+no_connect"))
    )
    (net (code "89") (name "unconnected-(U1A-PD13-Pad82)") (class "Default")
      (node (ref "U1") (pin "82") (pinfunction "PD13_82") (pintype "bidirectional+no_connect"))
    )
    (net (code "90") (name "unconnected-(U1A-PD14-Pad85)") (class "Default")
      (node (ref "U1") (pin "85") (pinfunction "PD14_85") (pintype "bidirectional+no_connect"))
    )
    (net (code "91") (name "unconnected-(U1A-PD15-Pad86)") (class "Default")
      (node (ref "U1") (pin "86") (pinfunction "PD15_86") (pintype "bidirectional+no_connect"))
    )
    (net (code "92") (name "unconnected-(U1A-PE0-Pad141)") (class "Default")
      (node (ref "U1") (pin "141") (pinfunction "PE0_141") (pintype "bidirectional+no_connect"))
    )
    (net (code "93") (name "unconnected-(U1A-PE1-Pad142)") (class "Default")
      (node (ref "U1") (pin "142") (pinfunction "PE1_142") (pintype "bidirectional+no_connect"))
    )
    (net (code "94") (name "unconnected-(U1A-PE2-Pad1)") (class "Default")
      (node (ref "U1") (pin "1") (pinfunction "PE2_1") (pintype "bidirectional+no_connect"))
    )
    (net (code "95") (name "unconnected-(U1A-PE3-Pad2)") (class "Default")
      (node (ref "U1") (pin "2") (pinfunction "PE3_2") (pintype "bidirectional+no_connect"))
    )
    (net (code "96") (name "unconnected-(U1A-PE4-Pad3)") (class "Default")
      (node (ref "U1") (pin "3") (pinfunction "PE4_3") (pintype "bidirectional+no_connect"))
    )
    (net (code "97") (name "unconnected-(U1A-PE5-Pad4)") (class "Default")
      (node (ref "U1") (pin "4") (pinfunction "PE5_4") (pintype "bidirectional+no_connect"))
    )
    (net (code "98") (name "unconnected-(U1A-PE6-Pad5)") (class "Default")
      (node (ref "U1") (pin "5") (pinfunction "PE6_5") (pintype "bidirectional+no_connect"))
    )
    (net (code "99") (name "unconnected-(U1A-PE7-Pad58)") (class "Default")
      (node (ref "U1") (pin "58") (pinfunction "PE7_58") (pintype "bidirectional+no_connect"))
    )
    (net (code "100") (name "unconnected-(U1A-PE8-Pad59)") (class "Default")
      (node (ref "U1") (pin "59") (pinfunction "PE8_59") (pintype "bidirectional+no_connect"))
    )
    (net (code "101") (name "unconnected-(U1A-PE10-Pad63)") (class "Default")
      (node (ref "U1") (pin "63") (pinfunction "PE10_63") (pintype "bidirectional+no_connect"))
    )
    (net (code "102") (name "unconnected-(U1A-PE11-Pad64)") (class "Default")
      (node (ref "U1") (pin "64") (pinfunction "PE11_64") (pintype "bidirectional+no_connect"))
    )
    (net (code "103") (name "unconnected-(U1A-PE12-Pad65)") (class "Default")
      (node (ref "U1") (pin "65") (pinfunction "PE12_65") (pintype "bidirectional+no_connect"))
    )
    (net (code "104") (name "unconnected-(U1A-PE13-Pad66)") (class "Default")
      (node (ref "U1") (pin "66") (pinfunction "PE13_66") (pintype "bidirectional+no_connect"))
    )
    (net (code "105") (name "unconnected-(U1A-PE14-Pad67)") (class "Default")
      (node (ref "U1") (pin "67") (pinfunction "PE14_67") (pintype "bidirectional+no_connect"))
    )
    (net (code "106") (name "unconnected-(U1A-PE15-Pad68)") (class "Default")
      (node (ref "U1") (pin "68") (pinfunction "PE15_68") (pintype "bidirectional+no_connect"))
    )
    (net (code "107") (name "unconnected-(U1A-PF0-Pad10)") (class "Default")
      (node (ref "U1") (pin "10") (pinfunction "PF0_10") (pintype "bidirectional+no_connect"))
    )
    (net (code "108") (name "unconnected-(U1A-PF1-Pad11)") (class "Default")
      (node (ref "U1") (pin "11") (pinfunction "PF1_11") (pintype "bidirectional+no_connect"))
    )
    (net (code "109") (name "unconnected-(U1A-PF2-Pad12)") (class "Default")
      (node (ref "U1") (pin "12") (pinfunction "PF2_12") (pintype "bidirectional+no_connect"))
    )
    (net (code "110") (name "unconnected-(U1A-PF6-Pad18)") (class "Default")
      (node (ref "U1") (pin "18") (pinfunction "PF6_18") (pintype "bidirectional+no_connect"))
    )
    (net (code "111") (name "unconnected-(U1A-PF7-Pad19)") (class "Default")
      (node (ref "U1") (pin "19") (pinfunction "PF7_19") (pintype "bidirectional+no_connect"))
    )
    (net (code "112") (name "unconnected-(U1A-PF8-Pad20)") (class "Default")
      (node (ref "U1") (pin "20") (pinfunction "PF8_20") (pintype "bidirectional+no_connect"))
    )
    (net (code "113") (name "unconnected-(U1A-PF9-Pad21)") (class "Default")
      (node (ref "U1") (pin "21") (pinfunction "PF9_21") (pintype "bidirectional+no_connect"))
    )
    (net (code "114") (name "unconnected-(U1A-PF10-Pad22)") (class "Default")
      (node (ref "U1") (pin "22") (pinfunction "PF10_22") (pintype "bidirectional+no_connect"))
    )
    (net (code "115") (name "unconnected-(U1A-PF11-Pad49)") (class "Default")
      (node (ref "U1") (pin "49") (pinfunction "PF11_49") (pintype "bidirectional+no_connect"))
    )
    (net (code "116") (name "unconnected-(U1A-PF12-Pad50)") (class "Default")
      (node (ref "U1") (pin "50") (pinfunction "PF12_50") (pintype "bidirectional+no_connect"))
    )
    (net (code "117") (name "unconnected-(U1A-PF13-Pad53)") (class "Default")
      (node (ref "U1") (pin "53") (pinfunction "PF13_53") (pintype "bidirectional+no_connect"))
    )
    (net (code "118") (name "unconnected-(U1A-PF14-Pad54)") (class "Default")
      (node (ref "U1") (pin "54") (pinfunction "PF14_54") (pintype "bidirectional+no_connect"))
    )
    (net (code "119") (name "unconnected-(U1A-PF15-Pad55)") (class "Default")
      (node (ref "U1") (pin "55") (pinfunction "PF15_55") (pintype "bidirectional+no_connect"))
    )
    (net (code "120") (name "unconnected-(U1B-PG0-Pad56)") (class "Default")
      (node (ref "U1") (pin "56") (pinfunction "PG0_56") (pintype "bidirectional+no_connect"))
    )
    (net (code "121") (name "unconnected-(U1B-PG1-Pad57)") (class "Default")
      (node (ref "U1") (pin "57") (pinfunction "PG1_57") (pintype "bidirectional+no_connect"))
    )
    (net (code "122") (name "unconnected-(U1B-PG2-Pad87)") (class "Default")
      (node (ref "U1") (pin "87") (pinfunction "PG2_87") (pintype "bidirectional+no_connect"))
    )
    (net (code "123") (name "unconnected-(U1B-PG3-Pad88)") (class "Default")
      (node (ref "U1") (pin "88") (pinfunction "PG3_88") (pintype "bidirectional+no_connect"))
    )
    (net (code "124") (name "unconnected-(U1B-PG4-Pad89)") (class "Default")
      (node (ref "U1") (pin "89") (pinfunction "PG4_89") (pintype "bidirectional+no_connect"))
    )
    (net (code "125") (name "unconnected-(U1B-PG6-Pad91)") (class "Default")
      (node (ref "U1") (pin "91") (pinfunction "PG6_91") (pintype "bidirectional+no_connect"))
    )
    (net (code "126") (name "unconnected-(U1B-PG7-Pad92)") (class "Default")
      (node (ref "U1") (pin "92") (pinfunction "PG7_92") (pintype "bidirectional+no_connect"))
    )
    (net (code "127") (name "unconnected-(U1B-PG8-Pad93)") (class "Default")
      (node (ref "U1") (pin "93") (pinfunction "PG8_93") (pintype "bidirectional+no_connect"))
    )
    (net (code "128") (name "unconnected-(U1B-PG9-Pad124)") (class "Default")
      (node (ref "U1") (pin "124") (pinfunction "PG9_124") (pintype "bidirectional+no_connect"))
    )
    (net (code "129") (name "unconnected-(U1B-PG10-Pad125)") (class "Default")
      (node (ref "U1") (pin "125") (pinfunction "PG10_125") (pintype "bidirectional+no_connect"))
    )
    (net (code "130") (name "unconnected-(U1B-PG11-Pad126)") (class "Default")
      (node (ref "U1") (pin "126") (pinfunction "PG11_126") (pintype "bidirectional+no_connect"))
    )
    (net (code "131") (name "unconnected-(U1B-PG12-Pad127)") (class "Default")
      (node (ref "U1") (pin "127") (pinfunction "PG12_127") (pintype "bidirectional+no_connect"))
    )
    (net (code "132") (name "unconnected-(U1B-PG13-Pad128)") (class "Default")
      (node (ref "U1") (pin "128") (pinfunction "PG13_128") (pintype "bidirectional+no_connect"))
    )
    (net (code "133") (name "unconnected-(U1B-PG14-Pad129)") (class "Default")
      (node (ref "U1") (pin "129") (pinfunction "PG14_129") (pintype "bidirectional+no_connect"))
    )
    (net (code "134") (name "unconnected-(U1B-PG15-Pad132)") (class "Default")
      (node (ref "U1") (pin "132") (pinfunction "PG15_132") (pintype "bidirectional+no_connect"))
    )
  )
)
